# Interface.net
KiCad netlist of a schematic drawn in Altium Designer
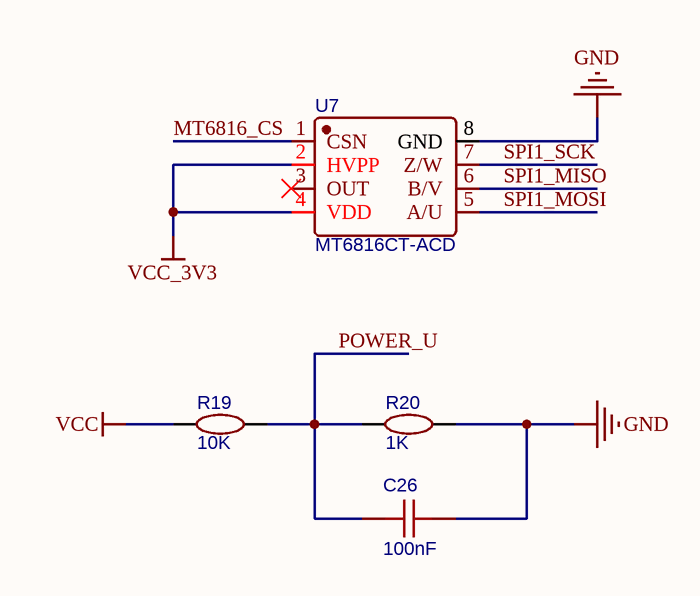
[diagram p0: Interface.SchDoc]

(export (version "E")
  (design (tool "Eeschema 10.0.6"))
  (components
    (comp (ref "C26")
      (value "100nF")
      (footprint "C0603")
      (fields
        (field (name "BOM_MANUFACTURER PART") "CL10B104KB8NNNC")
        (field (name "BOM_SUPPLIER PART") "C1591")
      )
      (libsource (lib "0.1uF") (part "100nF"))
    )
    (comp (ref "R19")
      (value "10K")
      (footprint "R0603")
      (fields
        (field (name "BOM_MANUFACTURER PART") "0603WAF1002T5E")
        (field (name "BOM_SUPPLIER PART") "C25804")
      )
      (libsource (lib "10K") (part "10K"))
    )
    (comp (ref "R20")
      (value "1K")
      (footprint "R0603")
      (fields
        (field (name "BOM_MANUFACTURER PART") "0603WAF1001T5E")
        (field (name "BOM_SUPPLIER PART") "C21190")
      )
      (libsource (lib "1K") (part "1K"))
    )
    (comp (ref "U7")
      (value "MT6816CT-ACD")
      (footprint "SOP-8_L5.0-W4.0-P1.27-LS6.0-BL")
      (fields (field (name "BOM_SUPPLIER PART") "C879560") (field (name "CONTRIBUTOR") "LCSC"))
      (libsource (lib "MT6816") (part "MT6816CT-ACD"))
    )
  )
  (nets
    (net (code "1") (name "/MT6816_CS") (class "Default")
      (node (ref "U7") (pin "1") (pinfunction "CSN_1") (pintype "passive"))
    )
    (net (code "2") (name "/POWER_U") (class "Default")
      (node (ref "C26") (pin "1") (pinfunction "1_1") (pintype "passive"))
      (node (ref "R19") (pin "2") (pinfunction "2_2") (pintype "passive"))
      (node (ref "R20") (pin "1") (pinfunction "1_1") (pintype "passive"))
    )
    (net (code "3") (name "/SPI1_MISO") (class "Default")
      (node (ref "U7") (pin "6") (pinfunction "B/V_6") (pintype "passive"))
    )
    (net (code "4") (name "/SPI1_MOSI") (class "Default")
      (node (ref "U7") (pin "5") (pinfunction "A/U_5") (pintype "passive"))
    )
    (net (code "5") (name "/SPI1_SCK") (class "Default")
      (node (ref "U7") (pin "7") (pinfunction "Z/W_7") (pintype "passive"))
    )
    (net (code "6") (name "GND") (class "Default")
      (node (ref "C26") (pin "2") (pinfunction "2_2") (pintype "passive"))
      (node (ref "R20") (pin "2") (pinfunction "2_2") (pintype "passive"))
      (node (ref "U7") (pin "8") (pinfunction "GND_8") (pintype "passive"))
    )
    (net (code "7") (name "VCC") (class "Default")
      (node (ref "R19") (pin "1") (pinfunction "1_1") (pintype "passive"))
    )
    (net (code "8") (name "VCC_3V3") (class "Default")
      (node (ref "U7") (pin "2") (pinfunction "HVPP_2") (pintype "passive"))
      (node (ref "U7") (pin "4") (pinfunction "VDD_4") (pintype "passive"))
    )
    (net (code "9") (name "unconnected-(U7-OUT-Pad3)") (class "Default")
      (node (ref "U7") (pin "3") (pinfunction "OUT_3") (pintype "passive+no_connect"))
    )
  )
)
